# adns3050_v6.net
KiCad netlist of a schematic drawn in EAGLE
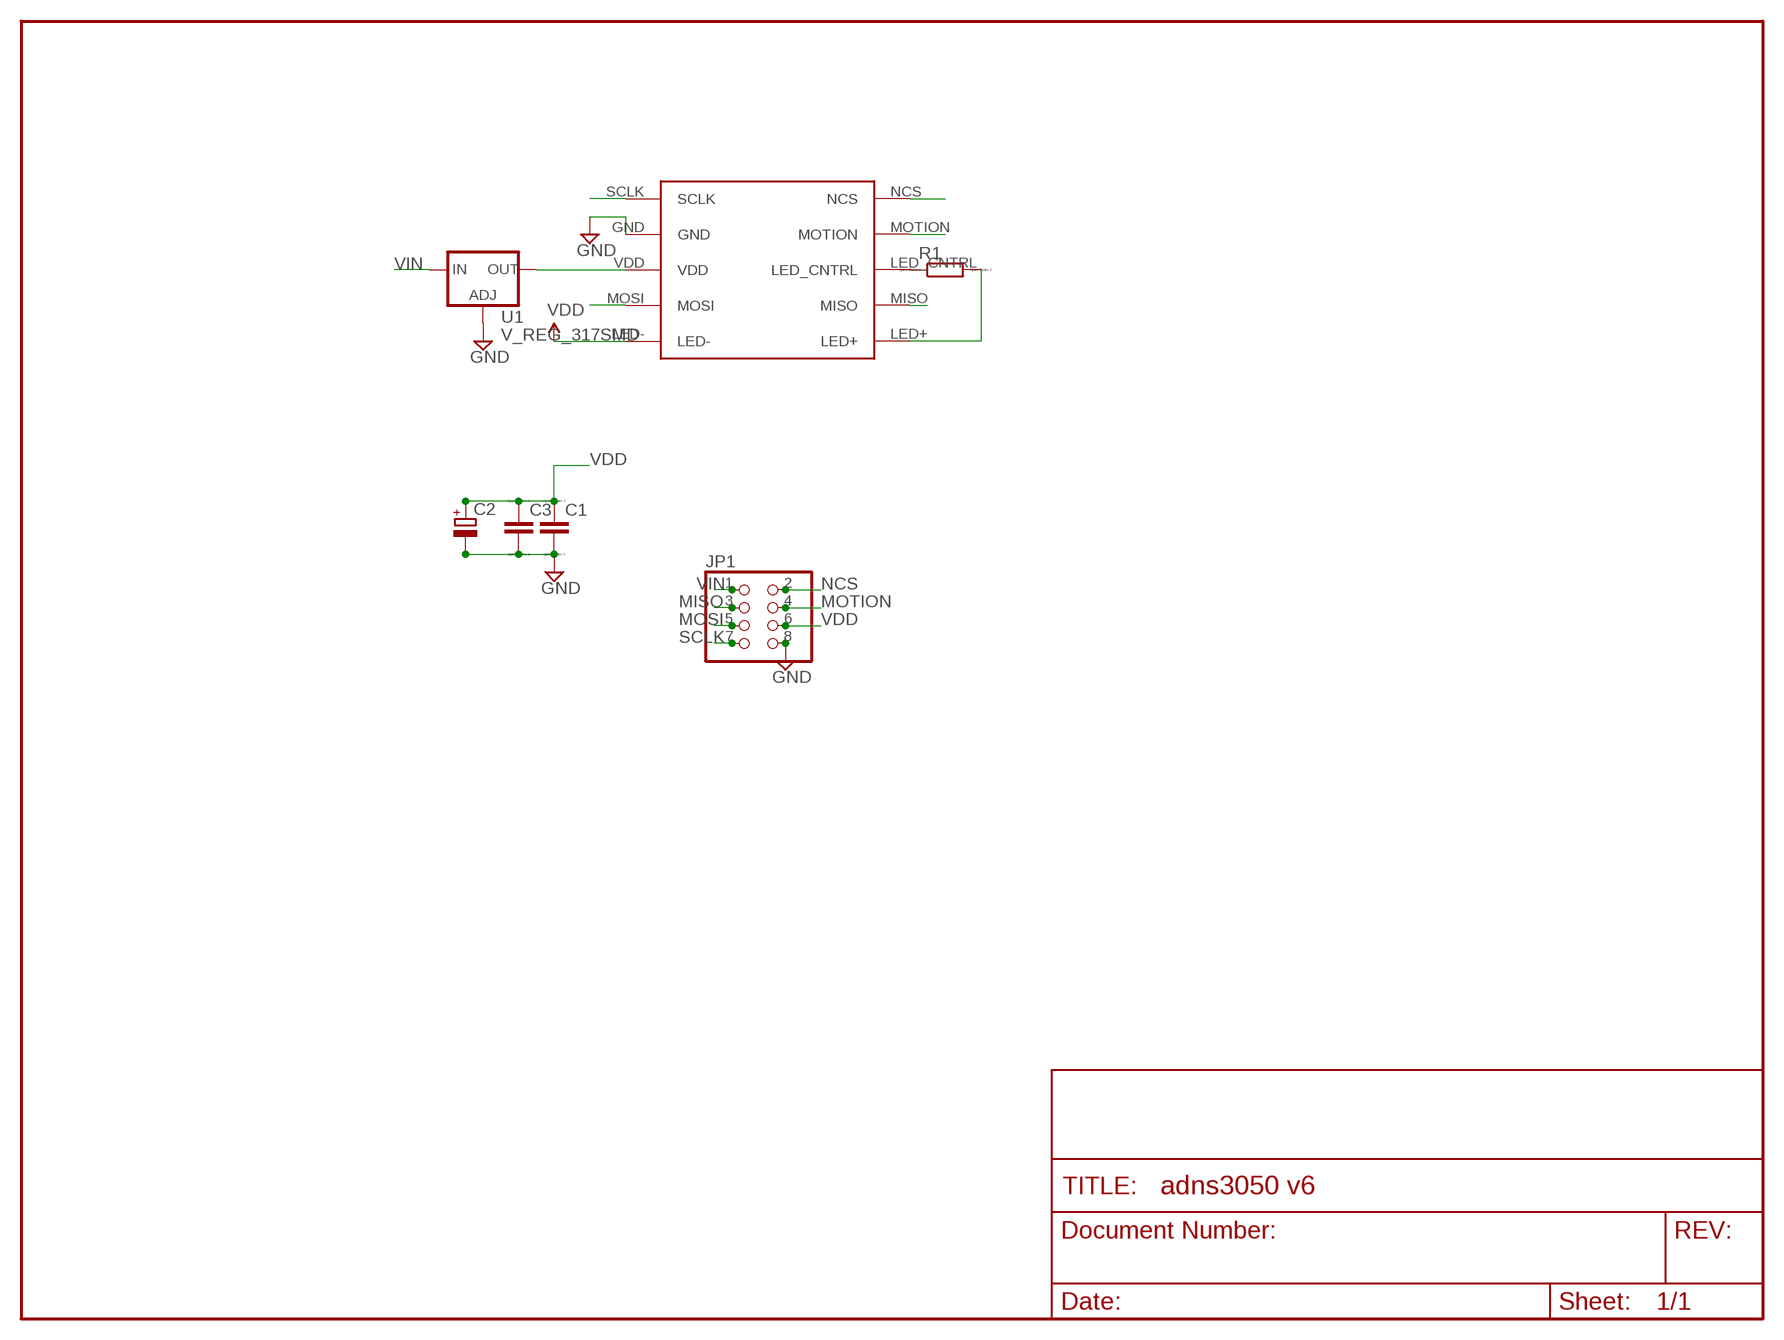
[diagram p0: schematic, sheet 1]

(export (version "E")
  (design (tool "Eeschema 10.0.6"))
  (components
    (comp (ref "C1")
      (value "CC0603")
      (footprint "eagle-import:C0603")
      (libsource (lib "eagle-import") (part "CC0603"))
    )
    (comp (ref "C2")
      (value "CPOL-EUR/2012-12R")
      (footprint "eagle-import:R_2012-12R")
      (libsource (lib "eagle-import") (part "CPOL-EUR/2012-12R"))
    )
    (comp (ref "C3")
      (value "CC0603")
      (footprint "eagle-import:C0603")
      (libsource (lib "eagle-import") (part "CC0603"))
    )
    (comp (ref "JP1")
      (value "PINHD-2X4")
      (footprint "eagle-import:2X04")
      (libsource (lib "eagle-import") (part "PINHD-2X4"))
    )
    (comp (ref "R1")
      (value "RR0603")
      (footprint "eagle-import:R0603")
      (libsource (lib "eagle-import") (part "RR0603"))
    )
    (comp (ref "U$1")
      (value "3050")
      (footprint "eagle-import:ADNS3")
      (libsource (lib "eagle-import") (part "3050"))
    )
    (comp (ref "U1")
      (value "V_REG_317SMD")
      (footprint "eagle-import:SOT223")
      (libsource (lib "eagle-import") (part "V_REG_317SMD"))
    )
  )
  (nets
    (net (code "1") (name "/MISO") (class "Default")
      (node (ref "JP1") (pin "3") (pinfunction "3_3") (pintype "passive"))
      (node (ref "U$1") (pin "MISO") (pinfunction "MISO_MISO") (pintype "bidirectional"))
    )
    (net (code "2") (name "/MOSI") (class "Default")
      (node (ref "JP1") (pin "5") (pinfunction "5_5") (pintype "passive"))
      (node (ref "U$1") (pin "MOSI") (pinfunction "MOSI_MOSI") (pintype "bidirectional"))
    )
    (net (code "3") (name "/MOTION") (class "Default")
      (node (ref "JP1") (pin "4") (pinfunction "4_4") (pintype "passive"))
      (node (ref "U$1") (pin "MOTION") (pinfunction "MOTION_MOTION") (pintype "bidirectional"))
    )
    (net (code "4") (name "/NCS") (class "Default")
      (node (ref "JP1") (pin "2") (pinfunction "2_2") (pintype "passive"))
      (node (ref "U$1") (pin "NCS") (pinfunction "NCS_NCS") (pintype "bidirectional"))
    )
    (net (code "5") (name "/SCLK") (class "Default")
      (node (ref "JP1") (pin "7") (pinfunction "7_7") (pintype "passive"))
      (node (ref "U$1") (pin "SCLK") (pinfunction "SCLK_SCLK") (pintype "bidirectional"))
    )
    (net (code "6") (name "/VIN") (class "Default")
      (node (ref "JP1") (pin "1") (pinfunction "1_1") (pintype "passive"))
      (node (ref "U1") (pin "3") (pinfunction "IN_3") (pintype "input"))
    )
    (net (code "7") (name "GND") (class "Default")
      (node (ref "C1") (pin "2") (pinfunction "2_2") (pintype "passive"))
      (node (ref "C2") (pin "-") (pinfunction "-_-") (pintype "passive"))
      (node (ref "C3") (pin "2") (pinfunction "2_2") (pintype "passive"))
      (node (ref "JP1") (pin "8") (pinfunction "8_8") (pintype "passive"))
      (node (ref "U$1") (pin "GND") (pinfunction "GND_GND") (pintype "bidirectional"))
      (node (ref "U1") (pin "1") (pinfunction "ADJ_1") (pintype "input"))
    )
    (net (code "8") (name "Net-(R1-Pad1)") (class "Default")
      (node (ref "R1") (pin "1") (pinfunction "1_1") (pintype "passive"))
      (node (ref "U$1") (pin "LED_CNTRL") (pinfunction "LED_CNTRL_LED_CNTRL") (pintype "bidirectional"))
    )
    (net (code "9") (name "Net-(R1-Pad2)") (class "Default")
      (node (ref "R1") (pin "2") (pinfunction "2_2") (pintype "passive"))
      (node (ref "U$1") (pin "LED+") (pinfunction "LED+_LED+") (pintype "bidirectional"))
    )
    (net (code "10") (name "VDD") (class "Default")
      (node (ref "C1") (pin "1") (pinfunction "1_1") (pintype "passive"))
      (node (ref "C2") (pin "+") (pinfunction "+_+") (pintype "passive"))
      (node (ref "C3") (pin "1") (pinfunction "1_1") (pintype "passive"))
      (node (ref "JP1") (pin "6") (pinfunction "6_6") (pintype "passive"))
      (node (ref "U$1") (pin "LED-") (pinfunction "LED-_LED-") (pintype "bidirectional"))
      (node (ref "U$1") (pin "VDD") (pinfunction "VDD_VDD") (pintype "bidirectional"))
      (node (ref "U1") (pin "2") (pinfunction "OUT_2") (pintype "output"))
    )
  )
)
